# attiny_at_batsense.net
KiCad netlist of a schematic drawn in EAGLE
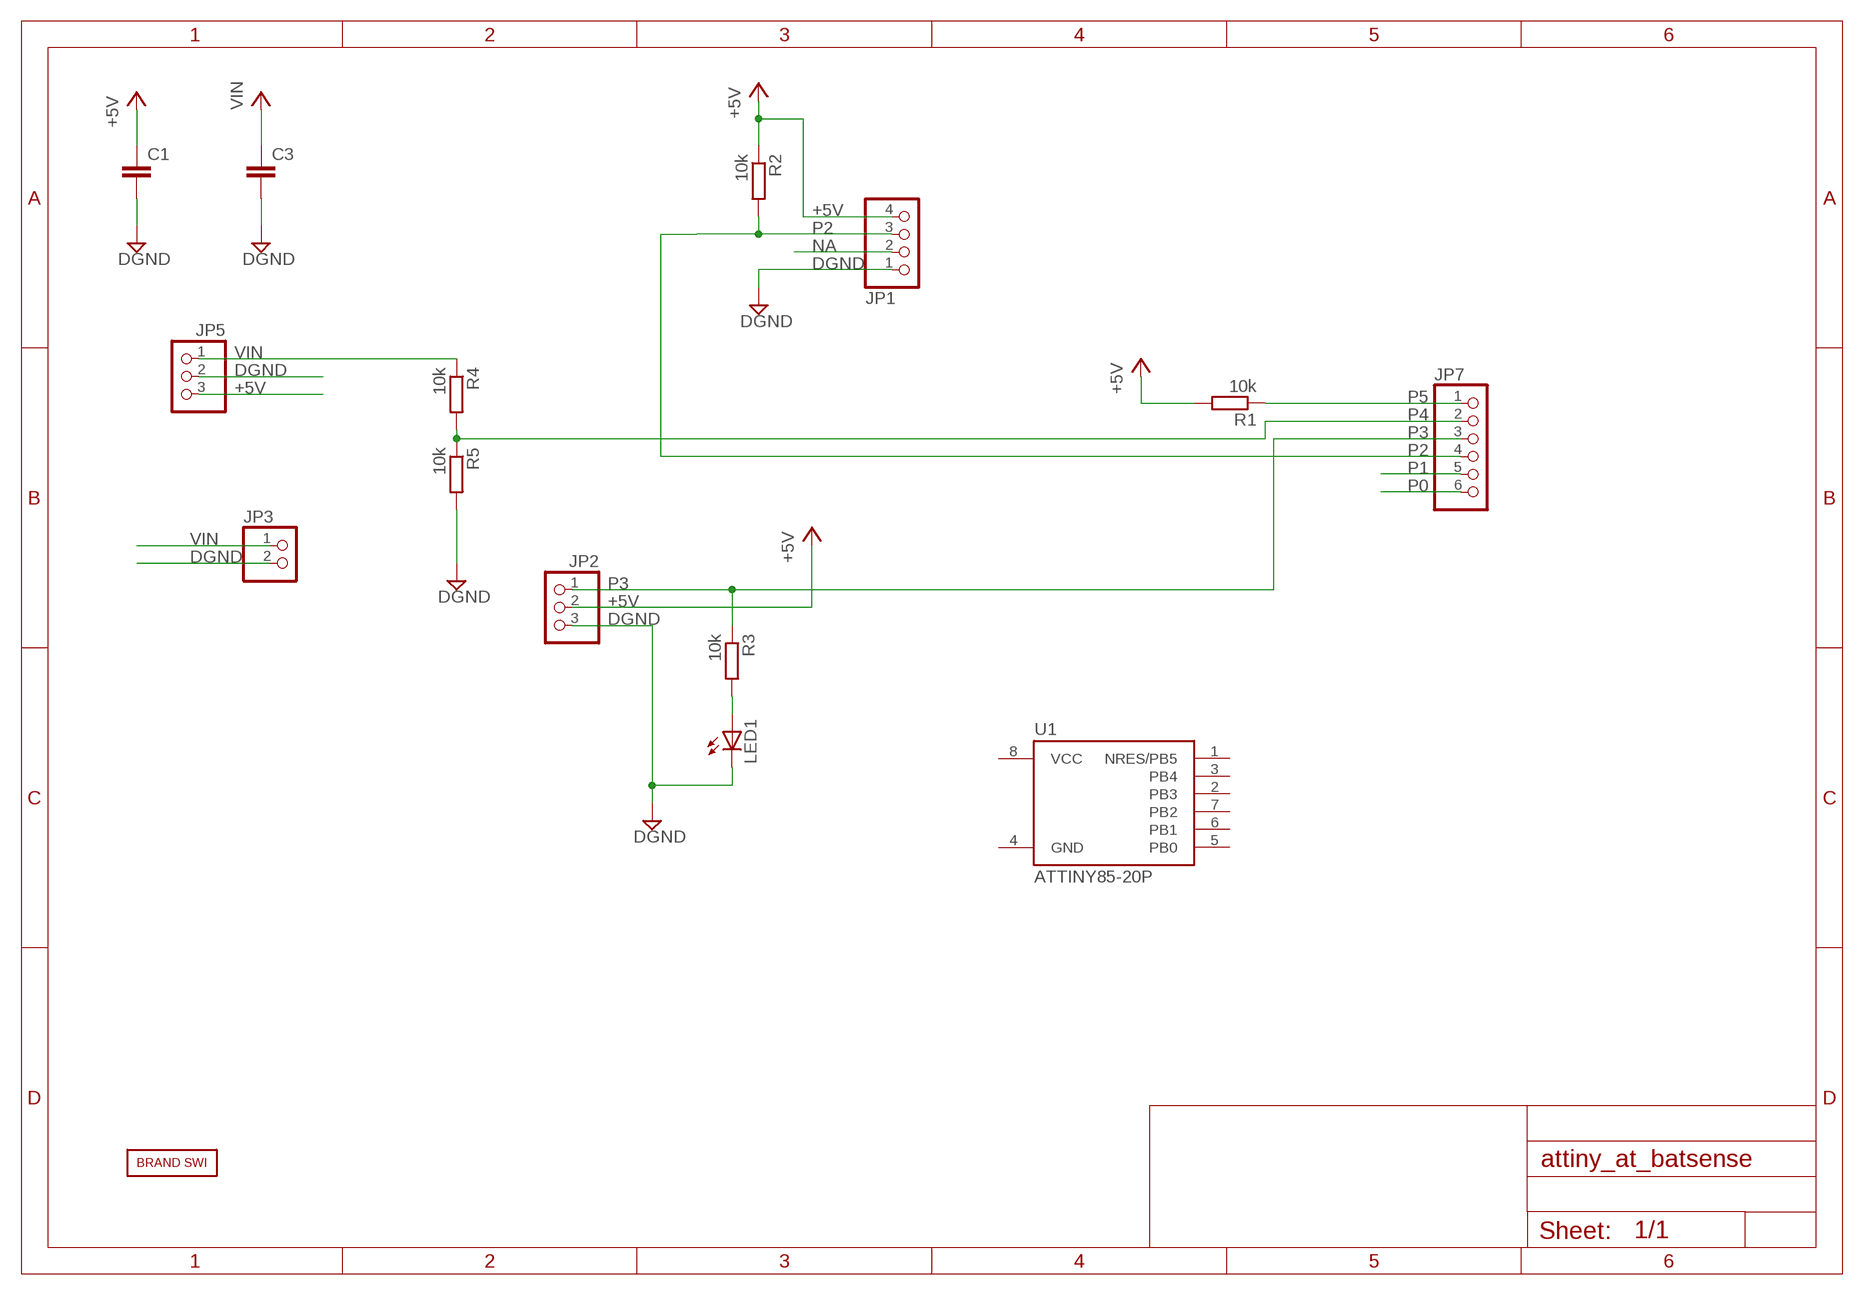
[diagram p0: schematic, sheet 1]

(export (version "E")
  (design (tool "Eeschema 10.0.6"))
  (components
    (comp (ref "C1")
      (value "C-EUC1210")
      (footprint "eagle-import:C1210")
      (libsource (lib "eagle-import") (part "C-EUC1210"))
    )
    (comp (ref "C3")
      (value "C-EUC1210")
      (footprint "eagle-import:C1210")
      (libsource (lib "eagle-import") (part "C-EUC1210"))
    )
    (comp (ref "JP1")
      (value "PINHD-1X4")
      (footprint "eagle-import:1X04")
      (libsource (lib "eagle-import") (part "PINHD-1X4"))
    )
    (comp (ref "JP2")
      (value "PINHD-1X3")
      (footprint "eagle-import:1X03")
      (libsource (lib "eagle-import") (part "PINHD-1X3"))
    )
    (comp (ref "JP3")
      (value "PINHD-1X2")
      (footprint "eagle-import:1X02")
      (libsource (lib "eagle-import") (part "PINHD-1X2"))
    )
    (comp (ref "JP5")
      (value "PINHD-1X3")
      (footprint "eagle-import:1X03")
      (libsource (lib "eagle-import") (part "PINHD-1X3"))
    )
    (comp (ref "JP7")
      (value "PINHD-1X6")
      (footprint "eagle-import:1X06")
      (libsource (lib "eagle-import") (part "PINHD-1X6"))
    )
    (comp (ref "LED1")
      (value "LED3MM")
      (footprint "eagle-import:LED3MM")
      (libsource (lib "eagle-import") (part "LED3MM"))
    )
    (comp (ref "R1")
      (value "10k")
      (footprint "eagle-import:R0805")
      (libsource (lib "eagle-import") (part "R-EU_R0805"))
    )
    (comp (ref "R2")
      (value "10k")
      (footprint "eagle-import:R0805")
      (libsource (lib "eagle-import") (part "R-EU_R0805"))
    )
    (comp (ref "R3")
      (value "10k")
      (footprint "eagle-import:R0805")
      (libsource (lib "eagle-import") (part "R-EU_R0805"))
    )
    (comp (ref "R4")
      (value "10k")
      (footprint "eagle-import:R0805")
      (libsource (lib "eagle-import") (part "R-EU_R0805"))
    )
    (comp (ref "R5")
      (value "10k")
      (footprint "eagle-import:R0805")
      (libsource (lib "eagle-import") (part "R-EU_R0805"))
    )
    (comp (ref "U$2")
      (value "BRAND_SWI5X7")
      (footprint "eagle-import:BRAND_SWI_5X7")
      (libsource (lib "eagle-import") (part "BRAND_SWI5X7"))
    )
    (comp (ref "U1")
      (value "ATTINY85-20P")
      (footprint "eagle-import:PDIP08_300MIL")
      (libsource (lib "eagle-import") (part "ATTINY85P-20"))
    )
  )
  (nets
    (net (code "1") (name "+5V") (class "Default")
      (node (ref "C1") (pin "1") (pinfunction "1_1") (pintype "passive"))
      (node (ref "JP1") (pin "4") (pinfunction "4_4") (pintype "passive"))
      (node (ref "JP2") (pin "2") (pinfunction "2_2") (pintype "passive"))
      (node (ref "JP5") (pin "3") (pinfunction "3_3") (pintype "passive"))
      (node (ref "R1") (pin "2") (pinfunction "2_2") (pintype "passive"))
      (node (ref "R2") (pin "1") (pinfunction "1_1") (pintype "passive"))
    )
    (net (code "2") (name "/GND") (class "Default")
      (node (ref "U1") (pin "4") (pinfunction "GND_4") (pintype "power_in"))
    )
    (net (code "3") (name "/NA") (class "Default")
      (node (ref "JP1") (pin "2") (pinfunction "2_2") (pintype "passive"))
    )
    (net (code "4") (name "/P0") (class "Default")
      (node (ref "JP7") (pin "6") (pinfunction "6_6") (pintype "passive"))
    )
    (net (code "5") (name "/P1") (class "Default")
      (node (ref "JP7") (pin "5") (pinfunction "5_5") (pintype "passive"))
    )
    (net (code "6") (name "/P2") (class "Default")
      (node (ref "JP1") (pin "3") (pinfunction "3_3") (pintype "passive"))
      (node (ref "JP7") (pin "4") (pinfunction "4_4") (pintype "passive"))
      (node (ref "R2") (pin "2") (pinfunction "2_2") (pintype "passive"))
    )
    (net (code "7") (name "/P3") (class "Default")
      (node (ref "JP2") (pin "1") (pinfunction "1_1") (pintype "passive"))
      (node (ref "JP7") (pin "3") (pinfunction "3_3") (pintype "passive"))
      (node (ref "R3") (pin "1") (pinfunction "1_1") (pintype "passive"))
    )
    (net (code "8") (name "/P4") (class "Default")
      (node (ref "JP7") (pin "2") (pinfunction "2_2") (pintype "passive"))
      (node (ref "R4") (pin "2") (pinfunction "2_2") (pintype "passive"))
      (node (ref "R5") (pin "1") (pinfunction "1_1") (pintype "passive"))
    )
    (net (code "9") (name "/P5") (class "Default")
      (node (ref "JP7") (pin "1") (pinfunction "1_1") (pintype "passive"))
      (node (ref "R1") (pin "1") (pinfunction "1_1") (pintype "passive"))
    )
    (net (code "10") (name "/VCC") (class "Default")
      (node (ref "U1") (pin "8") (pinfunction "VCC_8") (pintype "power_in"))
    )
    (net (code "11") (name "DGND") (class "Default")
      (node (ref "C1") (pin "2") (pinfunction "2_2") (pintype "passive"))
      (node (ref "C3") (pin "2") (pinfunction "2_2") (pintype "passive"))
      (node (ref "JP1") (pin "1") (pinfunction "1_1") (pintype "passive"))
      (node (ref "JP2") (pin "3") (pinfunction "3_3") (pintype "passive"))
      (node (ref "JP3") (pin "2") (pinfunction "2_2") (pintype "passive"))
      (node (ref "JP5") (pin "2") (pinfunction "2_2") (pintype "passive"))
      (node (ref "LED1") (pin "K") (pinfunction "C_K") (pintype "passive"))
      (node (ref "R5") (pin "2") (pinfunction "2_2") (pintype "passive"))
    )
    (net (code "12") (name "Net-(LED1-PadA)") (class "Default")
      (node (ref "LED1") (pin "A") (pinfunction "A_A") (pintype "passive"))
      (node (ref "R3") (pin "2") (pinfunction "2_2") (pintype "passive"))
    )
    (net (code "13") (name "VIN") (class "Default")
      (node (ref "C3") (pin "1") (pinfunction "1_1") (pintype "passive"))
      (node (ref "JP3") (pin "1") (pinfunction "1_1") (pintype "passive"))
      (node (ref "JP5") (pin "1") (pinfunction "1_1") (pintype "passive"))
      (node (ref "R4") (pin "1") (pinfunction "1_1") (pintype "passive"))
    )
    (net (code "14") (name "unconnected-(U1-NRES{slash}PB5-Pad1)") (class "Default")
      (node (ref "U1") (pin "1") (pinfunction "NRES/PB5_1") (pintype "bidirectional"))
    )
    (net (code "15") (name "unconnected-(U1-PB0-Pad5)") (class "Default")
      (node (ref "U1") (pin "5") (pinfunction "PB0_5") (pintype "bidirectional"))
    )
    (net (code "16") (name "unconnected-(U1-PB1-Pad6)") (class "Default")
      (node (ref "U1") (pin "6") (pinfunction "PB1_6") (pintype "bidirectional"))
    )
    (net (code "17") (name "unconnected-(U1-PB2-Pad7)") (class "Default")
      (node (ref "U1") (pin "7") (pinfunction "PB2_7") (pintype "bidirectional"))
    )
    (net (code "18") (name "unconnected-(U1-PB3-Pad2)") (class "Default")
      (node (ref "U1") (pin "2") (pinfunction "PB3_2") (pintype "bidirectional"))
    )
    (net (code "19") (name "unconnected-(U1-PB4-Pad3)") (class "Default")
      (node (ref "U1") (pin "3") (pinfunction "PB4_3") (pintype "bidirectional"))
    )
  )
)
